# cpu.net
KiCad netlist of a schematic drawn in Altium Designer
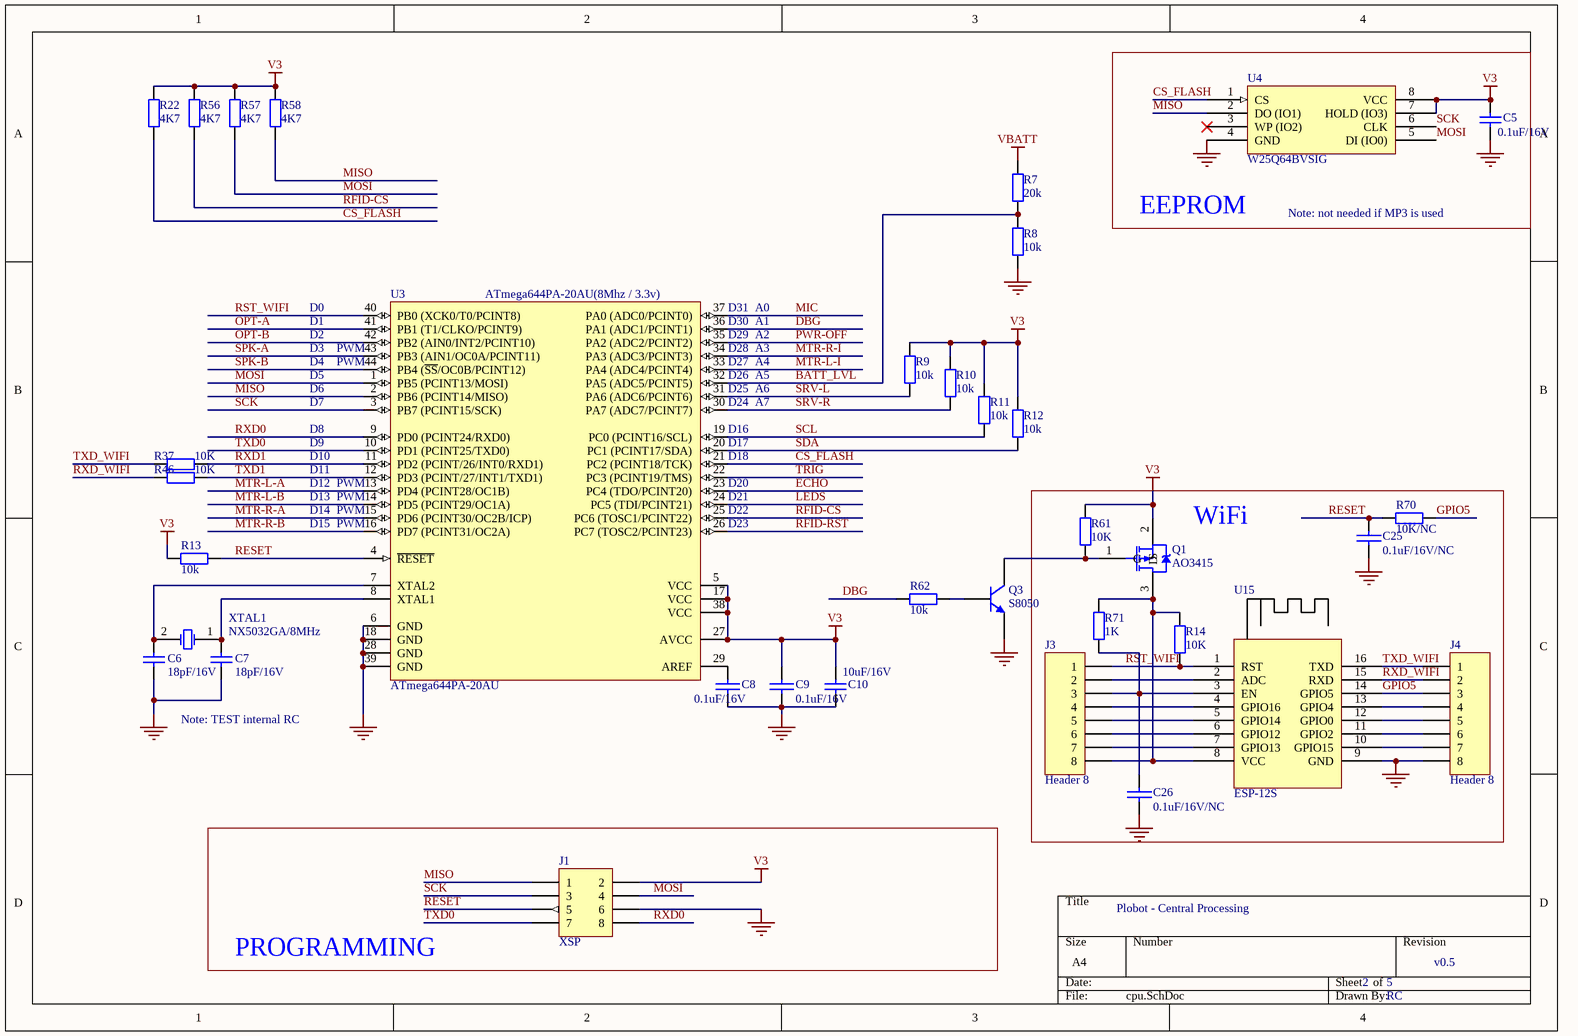
[diagram p0: cpu.SchDoc]

(export (version "E")
  (design (tool "Eeschema 10.0.6"))
  (components
    (comp (ref "C5")
      (value "0.1uF/16V")
      (footprint "CAPC1608N")
      (description "Capacitor")
      (fields (field (name "PUBLISHER") "Altium Limited"))
      (libsource (lib "*") (part "Cap"))
    )
    (comp (ref "C6")
      (value "18pF/16V")
      (footprint "CAPC1608N")
      (description "Capacitor")
      (fields (field (name "PUBLISHER") "Altium Limited"))
      (libsource (lib "*") (part "Cap"))
    )
    (comp (ref "C7")
      (value "18pF/16V")
      (footprint "CAPC1608N")
      (description "Capacitor")
      (fields (field (name "PUBLISHER") "Altium Limited"))
      (libsource (lib "*") (part "Cap"))
    )
    (comp (ref "C8")
      (value "0.1uF/16V")
      (footprint "CAPC1608N")
      (description "Capacitor")
      (libsource (lib "*") (part "CAP"))
    )
    (comp (ref "C9")
      (value "0.1uF/16V")
      (footprint "CAPC1608N")
      (description "Capacitor")
      (libsource (lib "*") (part "CAP"))
    )
    (comp (ref "C10")
      (value "10uF/16V")
      (footprint "CAPC1608N")
      (description "Capacitor")
      (fields (field (name "PUBLISHER") "Altium Limited"))
      (libsource (lib "main_pcb") (part "Cap_2"))
    )
    (comp (ref "C25")
      (value "0.1uF/16V/NC")
      (footprint "CAPC1608N")
      (description "Capacitor")
      (libsource (lib "*") (part "CAP"))
    )
    (comp (ref "C26")
      (value "0.1uF/16V/NC")
      (footprint "CAPC1608N")
      (description "Capacitor")
      (libsource (lib "*") (part "CAP"))
    )
    (comp (ref "J1")
      (value "XSP")
      (footprint "HDR2X4")
      (description "Header, 4-Pin, Dual row, Right Angle")
      (fields (field (name "PUBLISHER") "Altium Limited"))
      (libsource (lib "Miscellaneous Connectors") (part "Header 4X2H"))
    )
    (comp (ref "J3")
      (value "Header 8")
      (footprint "HDR1X8")
      (description "Header, 8-Pin")
      (fields (field (name "PUBLISHER") "Altium Limited"))
      (libsource (lib "") (part "Header 8_1"))
    )
    (comp (ref "J4")
      (value "Header 8")
      (footprint "HDR1X8")
      (description "Header, 8-Pin")
      (fields (field (name "PUBLISHER") "Altium Limited"))
      (libsource (lib "Miscellaneous Connectors") (part "Header 8"))
    )
    (comp (ref "Q1")
      (value "AO3415")
      (footprint "SOT23")
      (description "PMOS")
      (libsource (lib "SlotmachinePCBlib") (part "AO3415"))
    )
    (comp (ref "Q3")
      (value "S8050")
      (footprint "sot23")
      (description "NPN General Purpose Amplifier")
      (fields (field (name "PUBLISHER") "Altium Limited"))
      (libsource (lib "Miscellaneous Devices") (part "2N3904"))
    )
    (comp (ref "R7")
      (value "20k")
      (footprint "plobot_review:RESC1608N")
      (description "Resistor")
      (fields (field (name "PUBLISHER") "Altium Limited"))
      (libsource (lib "") (part "Res2_2"))
    )
    (comp (ref "R8")
      (value "10k")
      (footprint "plobot_review:RESC1608N")
      (description "Resistor")
      (fields (field (name "PUBLISHER") "Altium Limited"))
      (libsource (lib "") (part "Res2_2"))
    )
    (comp (ref "R9")
      (value "10k")
      (footprint "plobot_review:RESC1608N")
      (description "Resistor")
      (fields (field (name "PUBLISHER") "Altium Limited"))
      (libsource (lib "") (part "Res2_1"))
    )
    (comp (ref "R10")
      (value "10k")
      (footprint "plobot_review:RESC1608N")
      (description "Resistor")
      (fields (field (name "PUBLISHER") "Altium Limited"))
      (libsource (lib "") (part "Res2_1"))
    )
    (comp (ref "R11")
      (value "10k")
      (footprint "plobot_review:RESC1608N")
      (description "Resistor")
      (fields (field (name "PUBLISHER") "Altium Limited"))
      (libsource (lib "") (part "Res2_2"))
    )
    (comp (ref "R12")
      (value "10k")
      (footprint "plobot_review:RESC1608N")
      (description "Resistor")
      (fields (field (name "PUBLISHER") "Altium Limited"))
      (libsource (lib "") (part "Res2_1"))
    )
    (comp (ref "R13")
      (value "10k")
      (footprint "plobot_review:RESC1608N")
      (description "Resistor")
      (fields (field (name "PUBLISHER") "Altium Limited"))
      (libsource (lib "*") (part "Res2"))
    )
    (comp (ref "R14")
      (value "10K")
      (footprint "RESC1608N")
      (description "Resistor")
      (fields (field (name "PUBLISHER") "Altium Limited"))
      (libsource (lib "*") (part "Res2"))
    )
    (comp (ref "R22")
      (value "4K7")
      (footprint "RESC1608N")
      (description "Resistor")
      (fields (field (name "PUBLISHER") "Altium Limited"))
      (libsource (lib "") (part "Res2_1"))
    )
    (comp (ref "R37")
      (value "10K")
      (footprint "RESC1608N")
      (description "Resistor")
      (fields (field (name "PUBLISHER") "Altium Limited"))
      (libsource (lib "*") (part "Res2"))
    )
    (comp (ref "R46")
      (value "10K")
      (footprint "RESC1608N")
      (description "Resistor")
      (fields (field (name "PUBLISHER") "Altium Limited"))
      (libsource (lib "*") (part "Res2"))
    )
    (comp (ref "R56")
      (value "4K7")
      (footprint "RESC1608N")
      (description "Resistor")
      (fields (field (name "PUBLISHER") "Altium Limited"))
      (libsource (lib "") (part "Res2_1"))
    )
    (comp (ref "R57")
      (value "4K7")
      (footprint "RESC1608N")
      (description "Resistor")
      (fields (field (name "PUBLISHER") "Altium Limited"))
      (libsource (lib "") (part "Res2_1"))
    )
    (comp (ref "R58")
      (value "4K7")
      (footprint "RESC1608N")
      (description "Resistor")
      (fields (field (name "PUBLISHER") "Altium Limited"))
      (libsource (lib "") (part "Res2_1"))
    )
    (comp (ref "R61")
      (value "10K")
      (footprint "RESC1608N")
      (description "Resistor")
      (fields (field (name "PUBLISHER") "Altium Limited"))
      (libsource (lib "") (part "Res2_3"))
    )
    (comp (ref "R62")
      (value "10k")
      (footprint "RESC1608N")
      (description "Resistor")
      (fields (field (name "PUBLISHER") "Altium Limited"))
      (libsource (lib "") (part "Res2_2"))
    )
    (comp (ref "R70")
      (value "10K/NC")
      (footprint "RESC1608N")
      (description "Resistor")
      (fields (field (name "PUBLISHER") "Altium Limited"))
      (libsource (lib "") (part "Res2_2"))
    )
    (comp (ref "R71")
      (value "1K")
      (footprint "RESC1608N")
      (description "Resistor")
      (fields (field (name "PUBLISHER") "Altium Limited"))
      (libsource (lib "*") (part "Res2"))
    )
    (comp (ref "U3")
      (value "ATmega644PA-20AU")
      (footprint "atmega644p")
      (description "8-bit AVR Microcontroller, 2.7-5.5V, 20MHz, 64KB Flash, 2KB EEPROM, 4KB SRAM, 44-pin TQFP")
      (libsource (lib "*") (part "ATmega644-20AU"))
    )
    (comp (ref "U4")
      (value "W25Q64BVSIG")
      (footprint "plobot_review:W25Q64BVSIG")
      (libsource (lib "components") (part "W25Q64BVSIG"))
    )
    (comp (ref "U15")
      (value "ESP-12S")
      (footprint "ESP-12S")
      (libsource (lib "COMMODEVICES") (part "ESP-12S"))
    )
    (comp (ref "XTAL1")
      (value "NX5032GA/8MHz")
      (footprint "plobot_review:XTAL")
      (libsource (lib "components") (part "ABM7-8.000MHZ-D2Y-T"))
    )
  )
  (nets
    (net (code "1") (name "/BATT_LVL") (class "Default")
      (node (ref "R7") (pin "1") (pinfunction "1_1") (pintype "passive"))
      (node (ref "R8") (pin "2") (pinfunction "2_2") (pintype "passive"))
      (node (ref "U3") (pin "32") (pinfunction "PA5_(ADC5/PCINT5)_32") (pintype "bidirectional"))
    )
    (net (code "2") (name "/CS_FLASH") (class "Default")
      (node (ref "R22") (pin "2") (pinfunction "2_2") (pintype "passive"))
      (node (ref "U3") (pin "21") (pinfunction "PC2_(PCINT18/TCK)_21") (pintype "bidirectional"))
      (node (ref "U4") (pin "1") (pinfunction "CS_1") (pintype "input"))
    )
    (net (code "3") (name "/DBG") (class "Default")
      (node (ref "R62") (pin "1") (pinfunction "1_1") (pintype "passive"))
      (node (ref "U3") (pin "36") (pinfunction "PA1_(ADC1/PCINT1)_36") (pintype "bidirectional"))
    )
    (net (code "4") (name "/ECHO") (class "Default")
      (node (ref "U3") (pin "23") (pinfunction "PC4_(TDO/PCINT20)_23") (pintype "bidirectional"))
    )
    (net (code "5") (name "/GPIO5") (class "Default")
      (node (ref "J4") (pin "3") (pinfunction "3_3") (pintype "passive"))
      (node (ref "R70") (pin "2") (pinfunction "2_2") (pintype "passive"))
      (node (ref "U15") (pin "14") (pinfunction "GPIO5_14") (pintype "power_in"))
    )
    (net (code "6") (name "/LEDS") (class "Default")
      (node (ref "U3") (pin "24") (pinfunction "PC5_(TDI/PCINT21)_24") (pintype "bidirectional"))
    )
    (net (code "7") (name "/MIC") (class "Default")
      (node (ref "U3") (pin "37") (pinfunction "PA0_(ADC0/PCINT0)_37") (pintype "bidirectional"))
    )
    (net (code "8") (name "/MISO") (class "Default")
      (node (ref "J1") (pin "1") (pinfunction "1_1") (pintype "passive"))
      (node (ref "R58") (pin "2") (pinfunction "2_2") (pintype "passive"))
      (node (ref "U3") (pin "2") (pinfunction "PB6_(PCINT14/MISO)_2") (pintype "bidirectional"))
      (node (ref "U4") (pin "2") (pinfunction "DO_(IO1)_2") (pintype "passive"))
    )
    (net (code "9") (name "/MOSI") (class "Default")
      (node (ref "J1") (pin "4") (pinfunction "4_4") (pintype "passive"))
      (node (ref "R57") (pin "2") (pinfunction "2_2") (pintype "passive"))
      (node (ref "U3") (pin "1") (pinfunction "PB5_(PCINT13/MOSI)_1") (pintype "bidirectional"))
      (node (ref "U4") (pin "5") (pinfunction "DI_(IO0)_5") (pintype "passive"))
    )
    (net (code "10") (name "/MTR-L-A") (class "Default")
      (node (ref "U3") (pin "13") (pinfunction "PD4_(PCINT28/OC1B)_13") (pintype "bidirectional"))
    )
    (net (code "11") (name "/MTR-L-B") (class "Default")
      (node (ref "U3") (pin "14") (pinfunction "PD5_(PCINT29/OC1A)_14") (pintype "bidirectional"))
    )
    (net (code "12") (name "/MTR-L-I") (class "Default")
      (node (ref "U3") (pin "33") (pinfunction "PA4_(ADC4/PCINT4)_33") (pintype "bidirectional"))
    )
    (net (code "13") (name "/MTR-R-A") (class "Default")
      (node (ref "U3") (pin "15") (pinfunction "PD6_(PCINT30/OC2B/ICP)_15") (pintype "bidirectional"))
    )
    (net (code "14") (name "/MTR-R-B") (class "Default")
      (node (ref "U3") (pin "16") (pinfunction "PD7_(PCINT31/OC2A)_16") (pintype "bidirectional"))
    )
    (net (code "15") (name "/MTR-R-I") (class "Default")
      (node (ref "U3") (pin "34") (pinfunction "PA3_(ADC3/PCINT3)_34") (pintype "bidirectional"))
    )
    (net (code "16") (name "/OPT-A") (class "Default")
      (node (ref "U3") (pin "41") (pinfunction "PB1_(T1/CLKO/PCINT9)_41") (pintype "bidirectional"))
    )
    (net (code "17") (name "/OPT-B") (class "Default")
      (node (ref "U3") (pin "42") (pinfunction "PB2_(AIN0/INT2/PCINT10)_42") (pintype "bidirectional"))
    )
    (net (code "18") (name "/PWR-OFF") (class "Default")
      (node (ref "U3") (pin "35") (pinfunction "PA2_(ADC2/PCINT2)_35") (pintype "bidirectional"))
    )
    (net (code "19") (name "/RESET") (class "Default")
      (node (ref "C25") (pin "1") (pinfunction "1_1") (pintype "passive"))
      (node (ref "J1") (pin "5") (pinfunction "5_5") (pintype "output"))
      (node (ref "R13") (pin "2") (pinfunction "2_2") (pintype "passive"))
      (node (ref "R70") (pin "1") (pinfunction "1_1") (pintype "passive"))
      (node (ref "U3") (pin "4") (pinfunction "~{RESET}_4") (pintype "input"))
    )
    (net (code "20") (name "/RFID-CS") (class "Default")
      (node (ref "R56") (pin "2") (pinfunction "2_2") (pintype "passive"))
      (node (ref "U3") (pin "25") (pinfunction "PC6_(TOSC1/PCINT22)_25") (pintype "bidirectional"))
    )
    (net (code "21") (name "/RFID-RST") (class "Default")
      (node (ref "U3") (pin "26") (pinfunction "PC7_(TOSC2/PCINT23)_26") (pintype "bidirectional"))
    )
    (net (code "22") (name "/RST_WIFI") (class "Default")
      (node (ref "J3") (pin "1") (pinfunction "1_1") (pintype "passive"))
      (node (ref "R14") (pin "1") (pinfunction "1_1") (pintype "passive"))
      (node (ref "U15") (pin "1") (pinfunction "RST_1") (pintype "power_in"))
      (node (ref "U3") (pin "40") (pinfunction "PB0_(XCK0/T0/PCINT8)_40") (pintype "bidirectional"))
    )
    (net (code "23") (name "/RXD0") (class "Default")
      (node (ref "J1") (pin "8") (pinfunction "8_8") (pintype "passive"))
      (node (ref "U3") (pin "9") (pinfunction "PD0_(PCINT24/RXD0)_9") (pintype "bidirectional"))
    )
    (net (code "24") (name "/RXD1") (class "Default")
      (node (ref "R37") (pin "2") (pinfunction "2_2") (pintype "passive"))
      (node (ref "U3") (pin "11") (pinfunction "PD2_(PCINT/26/INT0/RXD1)_11") (pintype "bidirectional"))
    )
    (net (code "25") (name "/RXD_WIFI") (class "Default")
      (node (ref "J4") (pin "2") (pinfunction "2_2") (pintype "passive"))
      (node (ref "R46") (pin "1") (pinfunction "1_1") (pintype "passive"))
      (node (ref "U15") (pin "15") (pinfunction "RXD_15") (pintype "power_in"))
    )
    (net (code "26") (name "/SCK") (class "Default")
      (node (ref "J1") (pin "3") (pinfunction "3_3") (pintype "passive"))
      (node (ref "U3") (pin "3") (pinfunction "PB7_(PCINT15/SCK)_3") (pintype "bidirectional"))
      (node (ref "U4") (pin "6") (pinfunction "CLK_6") (pintype "passive"))
    )
    (net (code "27") (name "/SCL") (class "Default")
      (node (ref "R11") (pin "1") (pinfunction "1_1") (pintype "passive"))
      (node (ref "U3") (pin "19") (pinfunction "PC0_(PCINT16/SCL)_19") (pintype "bidirectional"))
    )
    (net (code "28") (name "/SDA") (class "Default")
      (node (ref "R12") (pin "2") (pinfunction "2_2") (pintype "passive"))
      (node (ref "U3") (pin "20") (pinfunction "PC1_(PCINT17/SDA)_20") (pintype "bidirectional"))
    )
    (net (code "29") (name "/SPK-A") (class "Default")
      (node (ref "U3") (pin "43") (pinfunction "PB3_(AIN1/OC0A/PCINT11)_43") (pintype "bidirectional"))
    )
    (net (code "30") (name "/SPK-B") (class "Default")
      (node (ref "U3") (pin "44") (pinfunction "PB4_(~{SS}/OC0B/PCINT12)_44") (pintype "bidirectional"))
    )
    (net (code "31") (name "/SRV-L") (class "Default")
      (node (ref "R9") (pin "2") (pinfunction "2_2") (pintype "passive"))
      (node (ref "U3") (pin "31") (pinfunction "PA6_(ADC6/PCINT6)_31") (pintype "bidirectional"))
    )
    (net (code "32") (name "/SRV-R") (class "Default")
      (node (ref "R10") (pin "2") (pinfunction "2_2") (pintype "passive"))
      (node (ref "U3") (pin "30") (pinfunction "PA7_(ADC7/PCINT7)_30") (pintype "bidirectional"))
    )
    (net (code "33") (name "/TRIG") (class "Default")
      (node (ref "U3") (pin "22") (pinfunction "PC3_(PCINT19/TMS)_22") (pintype "bidirectional"))
    )
    (net (code "34") (name "/TXD0") (class "Default")
      (node (ref "J1") (pin "7") (pinfunction "7_7") (pintype "passive"))
      (node (ref "U3") (pin "10") (pinfunction "PD1_(PCINT25/TXD0)_10") (pintype "bidirectional"))
    )
    (net (code "35") (name "/TXD1") (class "Default")
      (node (ref "R46") (pin "2") (pinfunction "2_2") (pintype "passive"))
      (node (ref "U3") (pin "12") (pinfunction "PD3_(PCINT/27/INT1/TXD1)_12") (pintype "bidirectional"))
    )
    (net (code "36") (name "/TXD_WIFI") (class "Default")
      (node (ref "J4") (pin "1") (pinfunction "1_1") (pintype "passive"))
      (node (ref "R37") (pin "1") (pinfunction "1_1") (pintype "passive"))
      (node (ref "U15") (pin "16") (pinfunction "TXD_16") (pintype "power_in"))
    )
    (net (code "37") (name "GND") (class "Default")
      (node (ref "C10") (pin "1") (pinfunction "1_1") (pintype "passive"))
      (node (ref "C25") (pin "2") (pinfunction "2_2") (pintype "passive"))
      (node (ref "C26") (pin "2") (pinfunction "2_2") (pintype "passive"))
      (node (ref "C5") (pin "2") (pinfunction "2_2") (pintype "passive"))
      (node (ref "C6") (pin "1") (pinfunction "1_1") (pintype "passive"))
      (node (ref "C7") (pin "1") (pinfunction "1_1") (pintype "passive"))
      (node (ref "C8") (pin "2") (pinfunction "2_2") (pintype "passive"))
      (node (ref "C9") (pin "2") (pinfunction "2_2") (pintype "passive"))
      (node (ref "J1") (pin "6") (pinfunction "6_6") (pintype "passive"))
      (node (ref "J4") (pin "8") (pinfunction "8_8") (pintype "passive"))
      (node (ref "Q3") (pin "1") (pinfunction "E_1") (pintype "passive"))
      (node (ref "R8") (pin "1") (pinfunction "1_1") (pintype "passive"))
      (node (ref "U15") (pin "9") (pinfunction "GND_9") (pintype "power_in"))
      (node (ref "U3") (pin "18") (pinfunction "GND_18") (pintype "power_in"))
      (node (ref "U3") (pin "28") (pinfunction "GND_28") (pintype "power_in"))
      (node (ref "U3") (pin "39") (pinfunction "GND_39") (pintype "power_in"))
      (node (ref "U3") (pin "6") (pinfunction "GND_6") (pintype "power_in"))
      (node (ref "U4") (pin "4") (pinfunction "GND_4") (pintype "power_in"))
    )
    (net (code "38") (name "Net-(Q1-D)") (class "Default")
      (node (ref "J3") (pin "8") (pinfunction "8_8") (pintype "passive"))
      (node (ref "Q1") (pin "3") (pinfunction "D_3") (pintype "passive"))
      (node (ref "R14") (pin "2") (pinfunction "2_2") (pintype "passive"))
      (node (ref "R71") (pin "2") (pinfunction "2_2") (pintype "passive"))
      (node (ref "U15") (pin "8") (pinfunction "VCC_8") (pintype "power_in"))
    )
    (net (code "39") (name "Net-(Q1-G)") (class "Default")
      (node (ref "Q1") (pin "1") (pinfunction "G_1") (pintype "passive"))
      (node (ref "Q3") (pin "3") (pinfunction "C_3") (pintype "passive"))
      (node (ref "R61") (pin "2") (pinfunction "2_2") (pintype "passive"))
    )
    (net (code "40") (name "Net-(Q3-B)") (class "Default")
      (node (ref "Q3") (pin "2") (pinfunction "B_2") (pintype "passive"))
      (node (ref "R62") (pin "2") (pinfunction "2_2") (pintype "passive"))
    )
    (net (code "41") (name "Net-(U3-AREF)") (class "Default")
      (node (ref "C8") (pin "1") (pinfunction "1_1") (pintype "passive"))
      (node (ref "U3") (pin "29") (pinfunction "AREF_29") (pintype "passive"))
    )
    (net (code "42") (name "Net-(U3-XTAL1)") (class "Default")
      (node (ref "C7") (pin "2") (pinfunction "2_2") (pintype "passive"))
      (node (ref "U3") (pin "8") (pinfunction "XTAL1_8") (pintype "passive"))
      (node (ref "XTAL1") (pin "1") (pinfunction "OSC1_1") (pintype "passive"))
    )
    (net (code "43") (name "Net-(U3-XTAL2)") (class "Default")
      (node (ref "C6") (pin "2") (pinfunction "2_2") (pintype "passive"))
      (node (ref "U3") (pin "7") (pinfunction "XTAL2_7") (pintype "passive"))
      (node (ref "XTAL1") (pin "2") (pinfunction "OSC2_2") (pintype "passive"))
    )
    (net (code "44") (name "Net-(U15-ADC)") (class "Default")
      (node (ref "J3") (pin "2") (pinfunction "2_2") (pintype "passive"))
      (node (ref "U15") (pin "2") (pinfunction "ADC_2") (pintype "power_in"))
    )
    (net (code "45") (name "Net-(U15-EN)") (class "Default")
      (node (ref "C26") (pin "1") (pinfunction "1_1") (pintype "passive"))
      (node (ref "J3") (pin "3") (pinfunction "3_3") (pintype "passive"))
      (node (ref "R71") (pin "1") (pinfunction "1_1") (pintype "passive"))
      (node (ref "U15") (pin "3") (pinfunction "EN_3") (pintype "power_in"))
    )
    (net (code "46") (name "Net-(U15-GPIO0)") (class "Default")
      (node (ref "J4") (pin "5") (pinfunction "5_5") (pintype "passive"))
      (node (ref "U15") (pin "12") (pinfunction "GPIO0_12") (pintype "power_in"))
    )
    (net (code "47") (name "Net-(U15-GPIO2)") (class "Default")
      (node (ref "J4") (pin "6") (pinfunction "6_6") (pintype "passive"))
      (node (ref "U15") (pin "11") (pinfunction "GPIO2_11") (pintype "power_in"))
    )
    (net (code "48") (name "Net-(U15-GPIO4)") (class "Default")
      (node (ref "J4") (pin "4") (pinfunction "4_4") (pintype "passive"))
      (node (ref "U15") (pin "13") (pinfunction "GPIO4_13") (pintype "power_in"))
    )
    (net (code "49") (name "Net-(U15-GPIO12)") (class "Default")
      (node (ref "J3") (pin "6") (pinfunction "6_6") (pintype "passive"))
      (node (ref "U15") (pin "6") (pinfunction "GPIO12_6") (pintype "power_in"))
    )
    (net (code "50") (name "Net-(U15-GPIO13)") (class "Default")
      (node (ref "J3") (pin "7") (pinfunction "7_7") (pintype "passive"))
      (node (ref "U15") (pin "7") (pinfunction "GPIO13_7") (pintype "power_in"))
    )
    (net (code "51") (name "Net-(U15-GPIO14)") (class "Default")
      (node (ref "J3") (pin "5") (pinfunction "5_5") (pintype "passive"))
      (node (ref "U15") (pin "5") (pinfunction "GPIO14_5") (pintype "power_in"))
    )
    (net (code "52") (name "Net-(U15-GPIO15)") (class "Default")
      (node (ref "J4") (pin "7") (pinfunction "7_7") (pintype "passive"))
      (node (ref "U15") (pin "10") (pinfunction "GPIO15_10") (pintype "power_in"))
    )
    (net (code "53") (name "Net-(U15-GPIO16)") (class "Default")
      (node (ref "J3") (pin "4") (pinfunction "4_4") (pintype "passive"))
      (node (ref "U15") (pin "4") (pinfunction "GPIO16_4") (pintype "power_in"))
    )
    (net (code "54") (name "V3") (class "Default")
      (node (ref "C10") (pin "2") (pinfunction "2_2") (pintype "passive"))
      (node (ref "C5") (pin "1") (pinfunction "1_1") (pintype "passive"))
      (node (ref "C9") (pin "1") (pinfunction "1_1") (pintype "passive"))
      (node (ref "J1") (pin "2") (pinfunction "2_2") (pintype "passive"))
      (node (ref "Q1") (pin "2") (pinfunction "S_2") (pintype "passive"))
      (node (ref "R10") (pin "1") (pinfunction "1_1") (pintype "passive"))
      (node (ref "R11") (pin "2") (pinfunction "2_2") (pintype "passive"))
      (node (ref "R12") (pin "1") (pinfunction "1_1") (pintype "passive"))
      (node (ref "R13") (pin "1") (pinfunction "1_1") (pintype "passive"))
      (node (ref "R22") (pin "1") (pinfunction "1_1") (pintype "passive"))
      (node (ref "R56") (pin "1") (pinfunction "1_1") (pintype "passive"))
      (node (ref "R57") (pin "1") (pinfunction "1_1") (pintype "passive"))
      (node (ref "R58") (pin "1") (pinfunction "1_1") (pintype "passive"))
      (node (ref "R61") (pin "1") (pinfunction "1_1") (pintype "passive"))
      (node (ref "R9") (pin "1") (pinfunction "1_1") (pintype "passive"))
      (node (ref "U3") (pin "17") (pinfunction "VCC_17") (pintype "power_in"))
      (node (ref "U3") (pin "27") (pinfunction "AVCC_27") (pintype "power_in"))
      (node (ref "U3") (pin "38") (pinfunction "VCC_38") (pintype "power_in"))
      (node (ref "U3") (pin "5") (pinfunction "VCC_5") (pintype "power_in"))
      (node (ref "U4") (pin "7") (pinfunction "HOLD_(IO3)_7") (pintype "passive"))
      (node (ref "U4") (pin "8") (pinfunction "VCC_8") (pintype "power_in"))
    )
    (net (code "55") (name "VBATT") (class "Default")
      (node (ref "R7") (pin "2") (pinfunction "2_2") (pintype "passive"))
    )
    (net (code "56") (name "unconnected-(U4-WP_(IO2)-Pad3)") (class "Default")
      (node (ref "U4") (pin "3") (pinfunction "WP_(IO2)_3") (pintype "passive+no_connect"))
    )
  )
)
